# LB_BIT_w7_FORK-v03_rev1.net
KiCad netlist of a schematic drawn in EAGLE
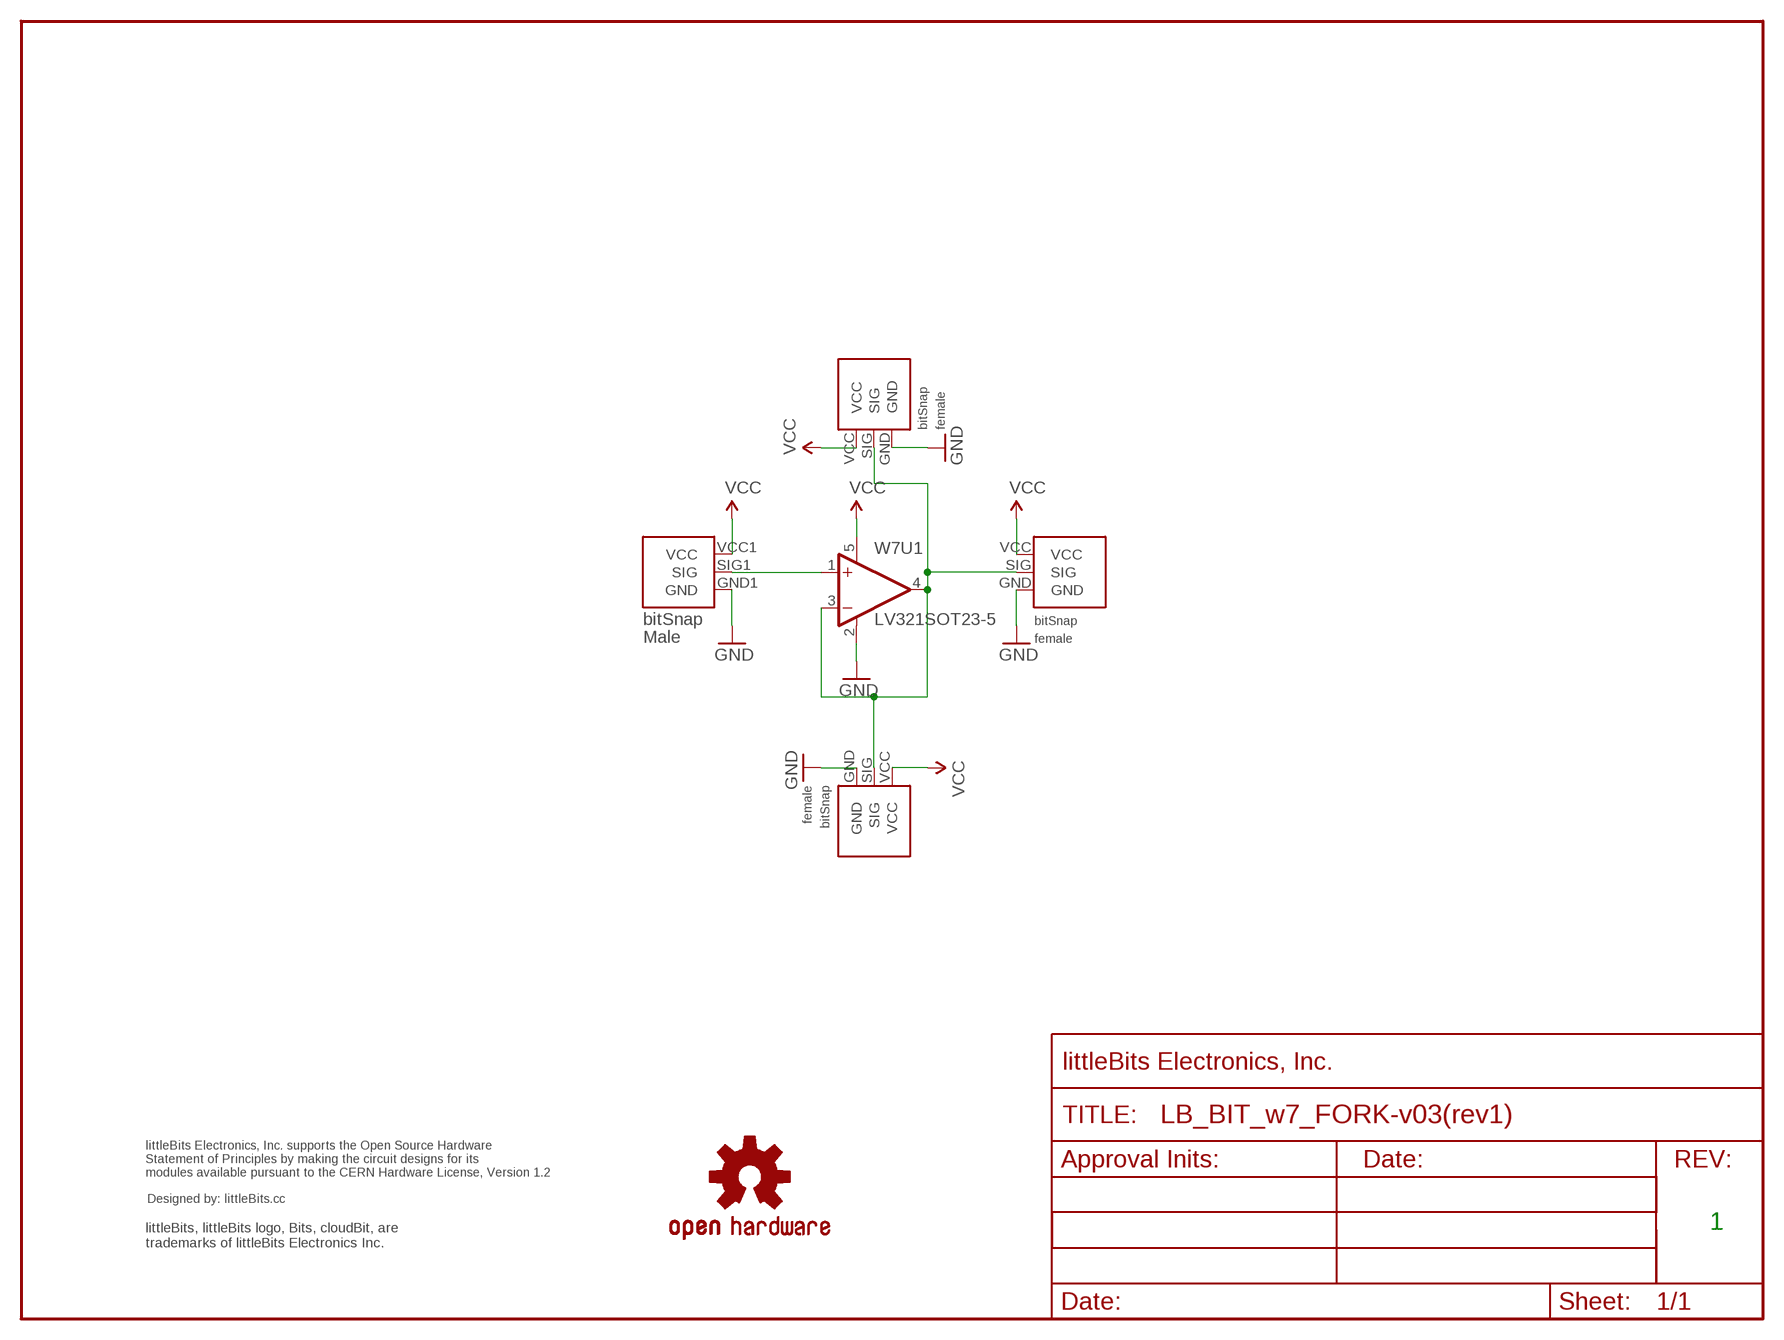
[diagram p0: schematic, sheet 1]

(export (version "E")
  (design (tool "Eeschema 10.0.6"))
  (components
    (comp (ref "FRAME1")
      (value "FRAME-LETTER-OHWOHW")
      (footprint "eagle-import:FABDWG01-OHW")
      (libsource (lib "eagle-import") (part "FRAME-LETTER-OHWOHW"))
    )
    (comp (ref "U$2")
      (value "OSHW-LOGOL")
      (footprint "eagle-import:OSHW-LOGO-L")
      (libsource (lib "eagle-import") (part "OSHW-LOGOL"))
    )
    (comp (ref "U$12")
      (value "OSHWCREDIT")
      (footprint "eagle-import:OSHWCREDIT")
      (libsource (lib "eagle-import") (part "OSHWCREDIT"))
    )
    (comp (ref "W7BSF1")
      (value "BITSNAP_V03_FEMALE")
      (footprint "eagle-import:BITSNAP_V03_FEMALE")
      (libsource (lib "eagle-import") (part "BITSNAP_V03_FEMALE"))
    )
    (comp (ref "W7BSF2")
      (value "BITSNAP_V03_FEMALE")
      (footprint "eagle-import:BITSNAP_V03_FEMALE")
      (libsource (lib "eagle-import") (part "BITSNAP_V03_FEMALE"))
    )
    (comp (ref "W7BSF3")
      (value "BITSNAP_V03_FEMALE")
      (footprint "eagle-import:BITSNAP_V03_FEMALE")
      (libsource (lib "eagle-import") (part "BITSNAP_V03_FEMALE"))
    )
    (comp (ref "W7BSM1")
      (value "BITSNAP_V03_MALE")
      (footprint "eagle-import:BITSNAP_V03_MALE")
      (libsource (lib "eagle-import") (part "BITSNAP_V03_MALE"))
    )
    (comp (ref "W7U1")
      (value "LV321SOT23-5")
      (footprint "eagle-import:SOT23-5")
      (libsource (lib "eagle-import") (part "LV321SOT23-5"))
    )
  )
  (nets
    (net (code "1") (name "GND") (class "Default")
      (node (ref "W7BSF1") (pin "GND") (pinfunction "GND_GND") (pintype "bidirectional"))
      (node (ref "W7BSF2") (pin "GND") (pinfunction "GND_GND") (pintype "bidirectional"))
      (node (ref "W7BSF3") (pin "GND") (pinfunction "GND_GND") (pintype "bidirectional"))
      (node (ref "W7BSM1") (pin "GND1") (pinfunction "GND_GND1") (pintype "bidirectional"))
      (node (ref "W7U1") (pin "2") (pinfunction "V-_2") (pintype "power_in"))
    )
    (net (code "2") (name "Net-(W7BSM1-SIG)") (class "Default")
      (node (ref "W7BSM1") (pin "SIG1") (pinfunction "SIG_SIG1") (pintype "bidirectional"))
      (node (ref "W7U1") (pin "1") (pinfunction "+IN_1") (pintype "input"))
    )
    (net (code "3") (name "Net-(W7U1--IN)") (class "Default")
      (node (ref "W7BSF1") (pin "SIG") (pinfunction "SIG_SIG") (pintype "bidirectional"))
      (node (ref "W7BSF2") (pin "SIG") (pinfunction "SIG_SIG") (pintype "bidirectional"))
      (node (ref "W7BSF3") (pin "SIG") (pinfunction "SIG_SIG") (pintype "bidirectional"))
      (node (ref "W7U1") (pin "3") (pinfunction "-IN_3") (pintype "input"))
      (node (ref "W7U1") (pin "4") (pinfunction "OUT_4") (pintype "output"))
    )
    (net (code "4") (name "VCC") (class "Default")
      (node (ref "W7BSF1") (pin "VCC") (pinfunction "VCC_VCC") (pintype "bidirectional"))
      (node (ref "W7BSF2") (pin "VCC") (pinfunction "VCC_VCC") (pintype "bidirectional"))
      (node (ref "W7BSF3") (pin "VCC") (pinfunction "VCC_VCC") (pintype "bidirectional"))
      (node (ref "W7BSM1") (pin "VCC1") (pinfunction "VCC_VCC1") (pintype "bidirectional"))
      (node (ref "W7U1") (pin "5") (pinfunction "V+_5") (pintype "power_in"))
    )
  )
)
